# upper_final_2.net
KiCad netlist of a schematic drawn in EAGLE
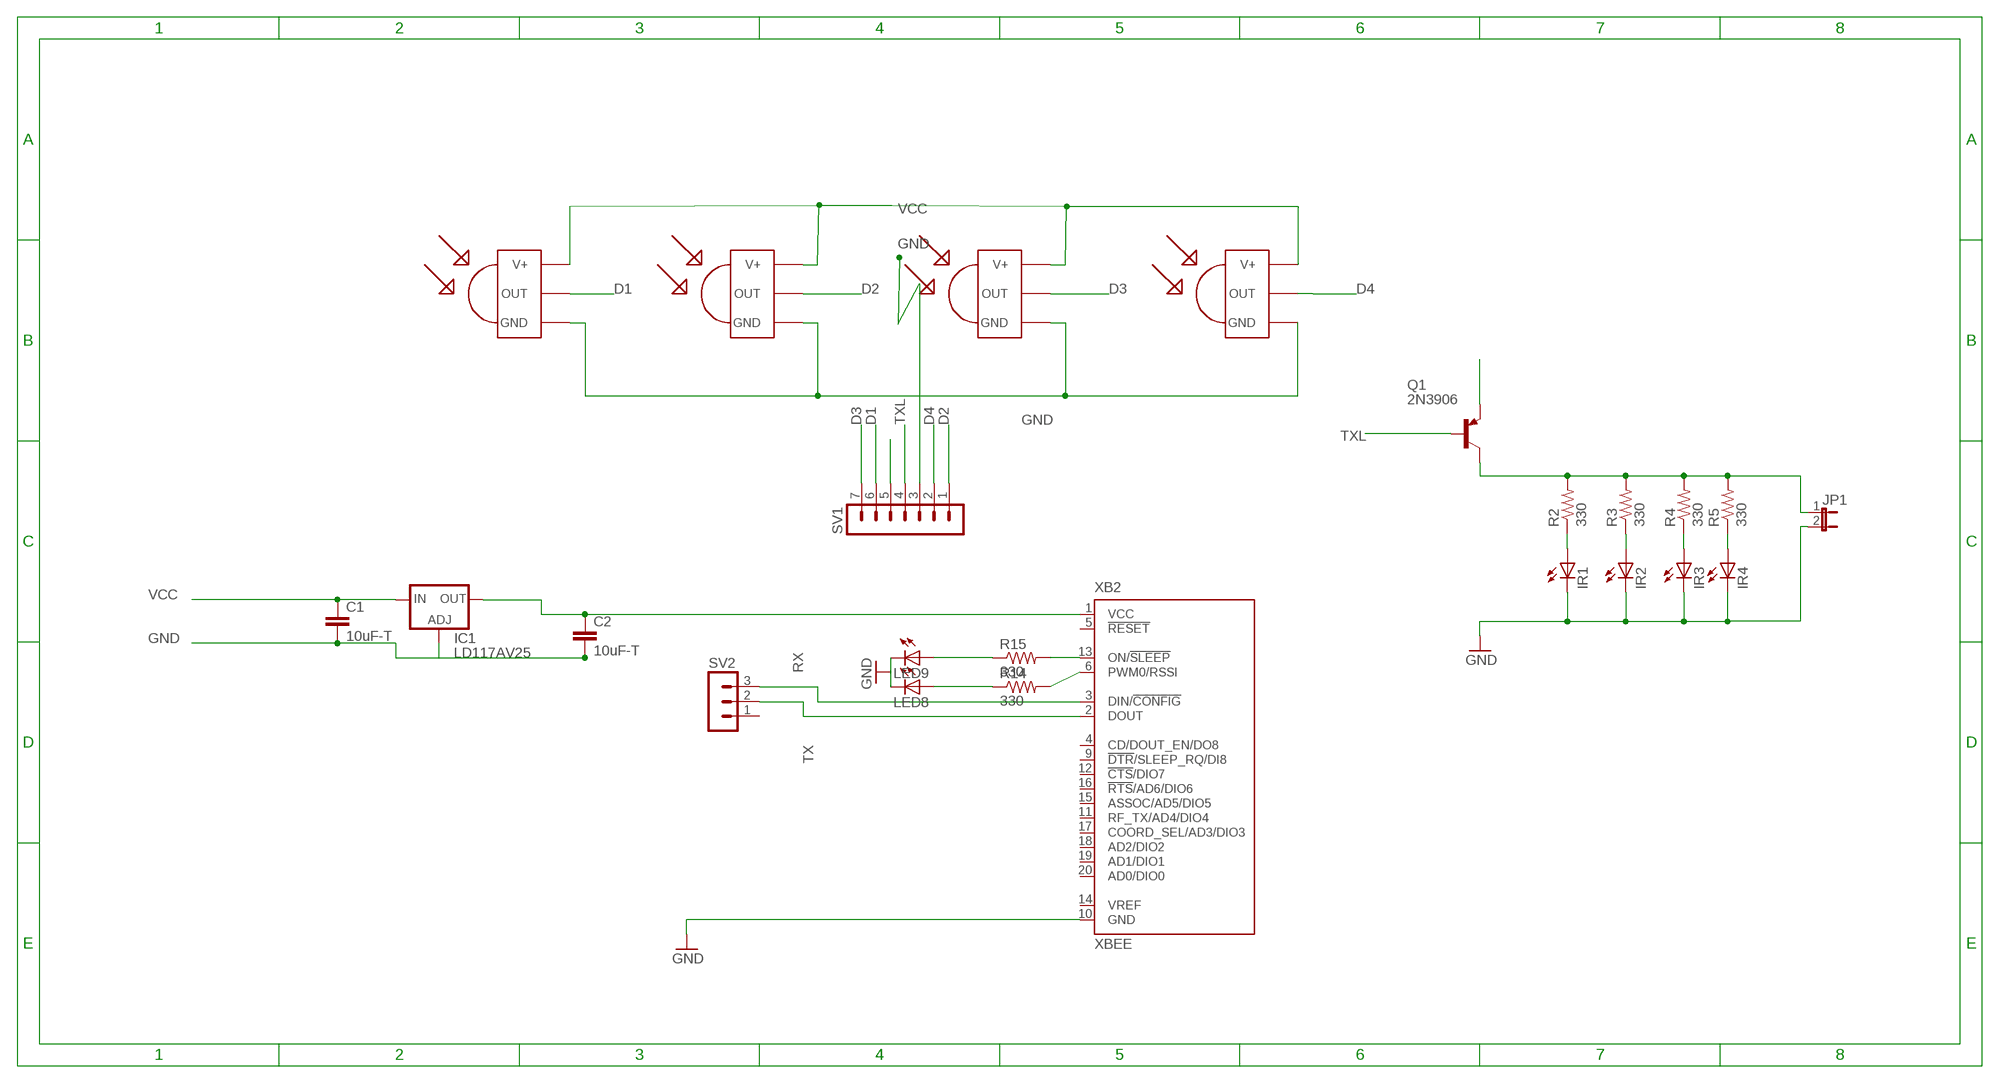
[diagram p0: schematic, sheet 1]

(export (version "E")
  (design (tool "Eeschema 10.0.6"))
  (components
    (comp (ref "C1")
      (value "10uF-T")
      (footprint "eagle-import:C025-024X044")
      (libsource (lib "eagle-import") (part "C-EU025-024X044"))
    )
    (comp (ref "C2")
      (value "10uF-T")
      (footprint "eagle-import:C025-024X044")
      (libsource (lib "eagle-import") (part "C-EU025-024X044"))
    )
    (comp (ref "IC1")
      (value "LD117AV25")
      (footprint "eagle-import:TO220L1")
      (libsource (lib "eagle-import") (part "LD117A?V25"))
    )
    (comp (ref "IR1")
      (value "SFH482")
      (footprint "eagle-import:SFH482")
      (libsource (lib "eagle-import") (part "SFH482"))
    )
    (comp (ref "IR2")
      (value "SFH482")
      (footprint "eagle-import:SFH482")
      (libsource (lib "eagle-import") (part "SFH482"))
    )
    (comp (ref "IR3")
      (value "SFH482")
      (footprint "eagle-import:SFH482")
      (libsource (lib "eagle-import") (part "SFH482"))
    )
    (comp (ref "IR4")
      (value "SFH482")
      (footprint "eagle-import:SFH482")
      (libsource (lib "eagle-import") (part "SFH482"))
    )
    (comp (ref "JP1")
      (value "JP1E")
      (footprint "eagle-import:JP1")
      (libsource (lib "eagle-import") (part "JP1E"))
    )
    (comp (ref "LED8")
      (value "LED3MM")
      (footprint "eagle-import:LED3MM")
      (libsource (lib "eagle-import") (part "LED3MM"))
    )
    (comp (ref "LED9")
      (value "LED3MM")
      (footprint "eagle-import:LED3MM")
      (libsource (lib "eagle-import") (part "LED3MM"))
    )
    (comp (ref "Q1")
      (value "2N3906")
      (footprint "eagle-import:TO92")
      (libsource (lib "eagle-import") (part "2N3906"))
    )
    (comp (ref "R2")
      (value "330")
      (footprint "eagle-import:0204_7")
      (libsource (lib "eagle-import") (part "resistor_R-US_0204/7"))
    )
    (comp (ref "R3")
      (value "330")
      (footprint "eagle-import:0204_7")
      (libsource (lib "eagle-import") (part "resistor_R-US_0204/7"))
    )
    (comp (ref "R4")
      (value "330")
      (footprint "eagle-import:0204_7")
      (libsource (lib "eagle-import") (part "resistor_R-US_0204/7"))
    )
    (comp (ref "R5")
      (value "330")
      (footprint "eagle-import:0204_7")
      (libsource (lib "eagle-import") (part "resistor_R-US_0204/7"))
    )
    (comp (ref "R14")
      (value "330")
      (footprint "eagle-import:0207_10")
      (libsource (lib "eagle-import") (part "R-US_0207/10"))
    )
    (comp (ref "R15")
      (value "330")
      (footprint "eagle-import:0207_10")
      (libsource (lib "eagle-import") (part "R-US_0207/10"))
    )
    (comp (ref "SV1")
      (value "MA07-1")
      (footprint "eagle-import:MA07-1")
      (libsource (lib "eagle-import") (part "MA07-1"))
    )
    (comp (ref "SV2")
      (value "MA03-1")
      (footprint "eagle-import:MA03-1")
      (libsource (lib "eagle-import") (part "MA03-1"))
    )
    (comp (ref "U$1")
      (value "TSOP1738")
      (footprint "eagle-import:TSOP17XX")
      (libsource (lib "eagle-import") (part "TSOP1738"))
    )
    (comp (ref "U$2")
      (value "TSOP1738")
      (footprint "eagle-import:TSOP17XX")
      (libsource (lib "eagle-import") (part "TSOP1738"))
    )
    (comp (ref "U$3")
      (value "TSOP1738")
      (footprint "eagle-import:TSOP17XX")
      (libsource (lib "eagle-import") (part "TSOP1738"))
    )
    (comp (ref "U$4")
      (value "TSOP1738")
      (footprint "eagle-import:TSOP17XX")
      (libsource (lib "eagle-import") (part "TSOP1738"))
    )
    (comp (ref "XB2")
      (value "XBEE")
      (footprint "eagle-import:XBEE")
      (fields (field (name "MPN") "XBP24-Z7UIT-004"))
      (libsource (lib "eagle-import") (part "XBEE"))
    )
  )
  (nets
    (net (code "1") (name "/D1") (class "Default")
      (node (ref "SV1") (pin "6") (pinfunction "6_6") (pintype "passive"))
      (node (ref "U$1") (pin "OUT") (pinfunction "OUT_OUT") (pintype "bidirectional"))
    )
    (net (code "2") (name "/D2") (class "Default")
      (node (ref "SV1") (pin "1") (pinfunction "1_1") (pintype "passive"))
      (node (ref "U$2") (pin "OUT") (pinfunction "OUT_OUT") (pintype "bidirectional"))
    )
    (net (code "3") (name "/D3") (class "Default")
      (node (ref "SV1") (pin "7") (pinfunction "7_7") (pintype "passive"))
      (node (ref "U$3") (pin "OUT") (pinfunction "OUT_OUT") (pintype "bidirectional"))
    )
    (net (code "4") (name "/D4") (class "Default")
      (node (ref "SV1") (pin "2") (pinfunction "2_2") (pintype "passive"))
      (node (ref "U$4") (pin "OUT") (pinfunction "OUT_OUT") (pintype "bidirectional"))
    )
    (net (code "5") (name "/RX") (class "Default")
      (node (ref "SV2") (pin "3") (pinfunction "3_3") (pintype "passive"))
      (node (ref "XB2") (pin "3") (pinfunction "DIN/~{CONFIG}_3") (pintype "input"))
    )
    (net (code "6") (name "/TX") (class "Default")
      (node (ref "SV2") (pin "2") (pinfunction "2_2") (pintype "passive"))
      (node (ref "XB2") (pin "2") (pinfunction "DOUT_2") (pintype "output"))
    )
    (net (code "7") (name "/TXL") (class "Default")
      (node (ref "Q1") (pin "2") (pinfunction "B_2") (pintype "passive"))
      (node (ref "SV1") (pin "4") (pinfunction "4_4") (pintype "passive"))
    )
    (net (code "8") (name "/VCC") (class "Default")
      (node (ref "C1") (pin "1") (pinfunction "1_1") (pintype "passive"))
      (node (ref "IC1") (pin "3") (pinfunction "IN_3") (pintype "input"))
      (node (ref "Q1") (pin "3") (pinfunction "E_3") (pintype "passive"))
      (node (ref "SV1") (pin "5") (pinfunction "5_5") (pintype "passive"))
      (node (ref "U$1") (pin "V+") (pinfunction "V+_V+") (pintype "bidirectional"))
      (node (ref "U$2") (pin "V+") (pinfunction "V+_V+") (pintype "bidirectional"))
      (node (ref "U$3") (pin "V+") (pinfunction "V+_V+") (pintype "bidirectional"))
      (node (ref "U$4") (pin "V+") (pinfunction "V+_V+") (pintype "bidirectional"))
    )
    (net (code "9") (name "GND") (class "Default")
      (node (ref "C1") (pin "2") (pinfunction "2_2") (pintype "passive"))
      (node (ref "C2") (pin "2") (pinfunction "2_2") (pintype "passive"))
      (node (ref "IC1") (pin "1") (pinfunction "ADJ_1") (pintype "input"))
      (node (ref "IR1") (pin "K") (pinfunction "C_K") (pintype "passive"))
      (node (ref "IR2") (pin "K") (pinfunction "C_K") (pintype "passive"))
      (node (ref "IR3") (pin "K") (pinfunction "C_K") (pintype "passive"))
      (node (ref "IR4") (pin "K") (pinfunction "C_K") (pintype "passive"))
      (node (ref "JP1") (pin "2") (pinfunction "2_2") (pintype "passive"))
      (node (ref "LED8") (pin "K") (pinfunction "C_K") (pintype "passive"))
      (node (ref "LED9") (pin "K") (pinfunction "C_K") (pintype "passive"))
      (node (ref "SV1") (pin "3") (pinfunction "3_3") (pintype "passive"))
      (node (ref "U$1") (pin "GND") (pinfunction "GND_GND") (pintype "bidirectional"))
      (node (ref "U$2") (pin "GND") (pinfunction "GND_GND") (pintype "bidirectional"))
      (node (ref "U$3") (pin "GND") (pinfunction "GND_GND") (pintype "bidirectional"))
      (node (ref "U$4") (pin "GND") (pinfunction "GND_GND") (pintype "bidirectional"))
      (node (ref "XB2") (pin "10") (pinfunction "GND_10") (pintype "power_in"))
    )
    (net (code "10") (name "Net-(IC1-OUT)") (class "Default")
      (node (ref "C2") (pin "1") (pinfunction "1_1") (pintype "passive"))
      (node (ref "IC1") (pin "2") (pinfunction "OUT_2") (pintype "passive"))
      (node (ref "XB2") (pin "1") (pinfunction "VCC_1") (pintype "power_in"))
    )
    (net (code "11") (name "Net-(IR1-PadA)") (class "Default")
      (node (ref "IR1") (pin "A") (pinfunction "A_A") (pintype "passive"))
      (node (ref "R2") (pin "1") (pinfunction "1_1") (pintype "passive"))
    )
    (net (code "12") (name "Net-(IR2-PadA)") (class "Default")
      (node (ref "IR2") (pin "A") (pinfunction "A_A") (pintype "passive"))
      (node (ref "R3") (pin "1") (pinfunction "1_1") (pintype "passive"))
    )
    (net (code "13") (name "Net-(IR3-PadA)") (class "Default")
      (node (ref "IR3") (pin "A") (pinfunction "A_A") (pintype "passive"))
      (node (ref "R4") (pin "1") (pinfunction "1_1") (pintype "passive"))
    )
    (net (code "14") (name "Net-(IR4-PadA)") (class "Default")
      (node (ref "IR4") (pin "A") (pinfunction "A_A") (pintype "passive"))
      (node (ref "R5") (pin "1") (pinfunction "1_1") (pintype "passive"))
    )
    (net (code "15") (name "Net-(LED8-PadA)") (class "Default")
      (node (ref "LED8") (pin "A") (pinfunction "A_A") (pintype "passive"))
      (node (ref "R14") (pin "1") (pinfunction "1_1") (pintype "passive"))
    )
    (net (code "16") (name "Net-(LED9-PadA)") (class "Default")
      (node (ref "LED9") (pin "A") (pinfunction "A_A") (pintype "passive"))
      (node (ref "R15") (pin "1") (pinfunction "1_1") (pintype "passive"))
    )
    (net (code "17") (name "Net-(Q1-C)") (class "Default")
      (node (ref "JP1") (pin "1") (pinfunction "1_1") (pintype "passive"))
      (node (ref "Q1") (pin "1") (pinfunction "C_1") (pintype "passive"))
      (node (ref "R2") (pin "2") (pinfunction "2_2") (pintype "passive"))
      (node (ref "R3") (pin "2") (pinfunction "2_2") (pintype "passive"))
      (node (ref "R4") (pin "2") (pinfunction "2_2") (pintype "passive"))
      (node (ref "R5") (pin "2") (pinfunction "2_2") (pintype "passive"))
    )
    (net (code "18") (name "Net-(XB2-ON{slash}~{SLEEP})") (class "Default")
      (node (ref "R15") (pin "2") (pinfunction "2_2") (pintype "passive"))
      (node (ref "XB2") (pin "13") (pinfunction "ON/~{SLEEP}_13") (pintype "output"))
    )
    (net (code "19") (name "Net-(XB2-PWM0{slash}RSSI)") (class "Default")
      (node (ref "R14") (pin "2") (pinfunction "2_2") (pintype "passive"))
      (node (ref "XB2") (pin "6") (pinfunction "PWM0/RSSI_6") (pintype "output"))
    )
    (net (code "20") (name "unconnected-(SV2-Pad1)") (class "Default")
      (node (ref "SV2") (pin "1") (pinfunction "1_1") (pintype "passive"))
    )
    (net (code "21") (name "unconnected-(XB2-AD0{slash}DIO0-Pad20)") (class "Default")
      (node (ref "XB2") (pin "20") (pinfunction "AD0/DIO0_20") (pintype "bidirectional"))
    )
    (net (code "22") (name "unconnected-(XB2-AD1{slash}DIO1-Pad19)") (class "Default")
      (node (ref "XB2") (pin "19") (pinfunction "AD1/DIO1_19") (pintype "bidirectional"))
    )
    (net (code "23") (name "unconnected-(XB2-AD2{slash}DIO2-Pad18)") (class "Default")
      (node (ref "XB2") (pin "18") (pinfunction "AD2/DIO2_18") (pintype "bidirectional"))
    )
    (net (code "24") (name "unconnected-(XB2-ASSOC{slash}AD5{slash}DIO5-Pad15)") (class "Default")
      (node (ref "XB2") (pin "15") (pinfunction "ASSOC/AD5/DIO5_15") (pintype "bidirectional"))
    )
    (net (code "25") (name "unconnected-(XB2-CD{slash}DOUT_EN{slash}DO8-Pad4)") (class "Default")
      (node (ref "XB2") (pin "4") (pinfunction "CD/DOUT_EN/DO8_4") (pintype "output"))
    )
    (net (code "26") (name "unconnected-(XB2-COORD_SEL{slash}AD3{slash}DIO3-Pad17)") (class "Default")
      (node (ref "XB2") (pin "17") (pinfunction "COORD_SEL/AD3/DIO3_17") (pintype "bidirectional"))
    )
    (net (code "27") (name "unconnected-(XB2-RF_TX{slash}AD4{slash}DIO4-Pad11)") (class "Default")
      (node (ref "XB2") (pin "11") (pinfunction "RF_TX/AD4/DIO4_11") (pintype "bidirectional"))
    )
    (net (code "28") (name "unconnected-(XB2-VREF-Pad14)") (class "Default")
      (node (ref "XB2") (pin "14") (pinfunction "VREF_14") (pintype "input"))
    )
    (net (code "29") (name "unconnected-(XB2-~{CTS}{slash}DIO7-Pad12)") (class "Default")
      (node (ref "XB2") (pin "12") (pinfunction "~{CTS}/DIO7_12") (pintype "bidirectional"))
    )
    (net (code "30") (name "unconnected-(XB2-~{DTR}{slash}SLEEP_RQ{slash}DI8-Pad9)") (class "Default")
      (node (ref "XB2") (pin "9") (pinfunction "~{DTR}/SLEEP_RQ/DI8_9") (pintype "bidirectional"))
    )
    (net (code "31") (name "unconnected-(XB2-~{RESET}-Pad5)") (class "Default")
      (node (ref "XB2") (pin "5") (pinfunction "~{RESET}_5") (pintype "input"))
    )
    (net (code "32") (name "unconnected-(XB2-~{RTS}{slash}AD6{slash}DIO6-Pad16)") (class "Default")
      (node (ref "XB2") (pin "16") (pinfunction "~{RTS}/AD6/DIO6_16") (pintype "bidirectional"))
    )
  )
)
